# C-09_BOOT_CFG.net
KiCad netlist of a schematic drawn in Altium Designer
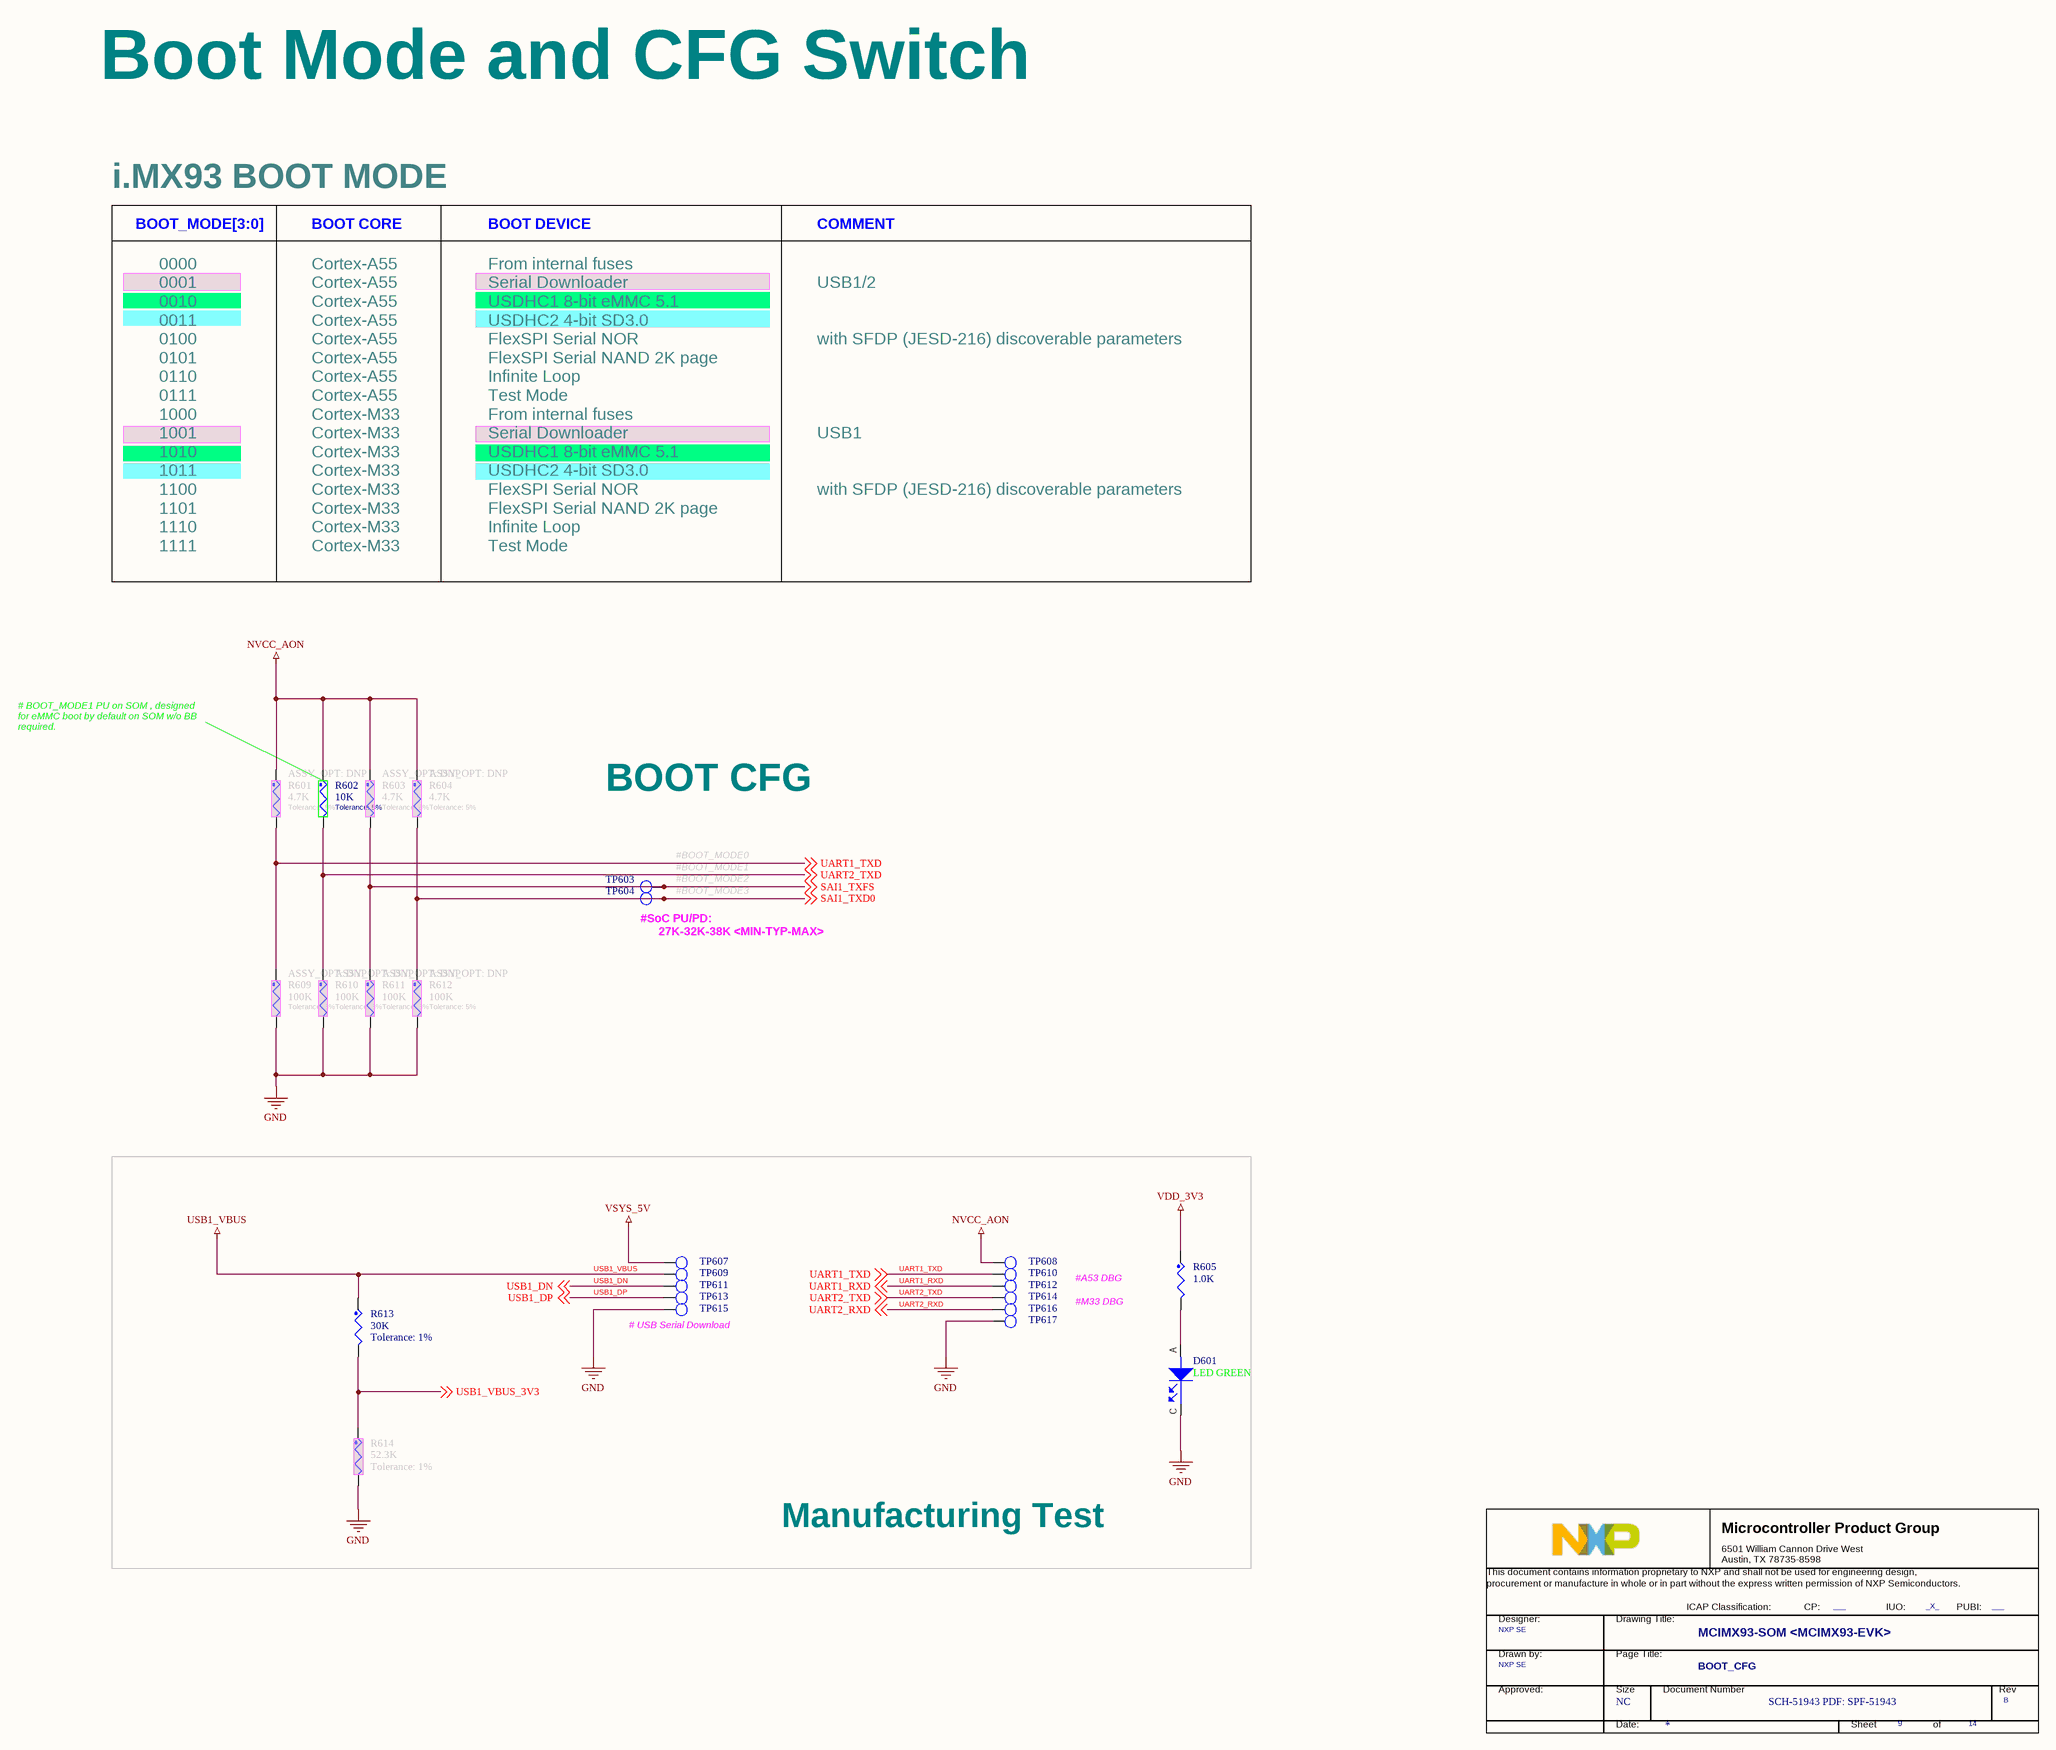
[diagram p0: C-09 BOOT_CFG.SchDoc]

(export (version "E")
  (design (tool "Eeschema 10.0.6"))
  (components
    (comp (ref "D601")
      (value "LED GREEN")
      (footprint "LED_0603")
      (description "LED GRN SGL 25MA SMT 0603")
      (fields (field (name "VOLTAGE") "2V"))
      (libsource (lib "*") (part "LED"))
    )
    (comp (ref "R601")
      (value "4.7K")
      (footprint "0402_CC")
      (description "RES MF 4.7K 1/10W 5% AEC-Q200 0402")
      (fields (field (name "ASSY_OPT") "DNP") (field (name "TOLERANCE") "5%") (field (name "VOLTAGE") "50V"))
      (libsource (lib "*") (part "RES"))
    )
    (comp (ref "R602")
      (value "10K")
      (footprint "0402_CC")
      (description "RES MF 10K 1/16W 5% 0402")
      (fields (field (name "TOLERANCE") "5%"))
      (libsource (lib "*") (part "RES"))
    )
    (comp (ref "R603")
      (value "4.7K")
      (footprint "0402_CC")
      (description "RES MF 4.7K 1/10W 5% AEC-Q200 0402")
      (fields (field (name "ASSY_OPT") "DNP") (field (name "VOLTAGE") "50V") (field (name "TOLERANCE") "5%"))
      (libsource (lib "*") (part "RES"))
    )
    (comp (ref "R604")
      (value "4.7K")
      (footprint "0402_CC")
      (description "RES MF 4.7K 1/10W 5% AEC-Q200 0402")
      (fields (field (name "ASSY_OPT") "DNP") (field (name "VOLTAGE") "50V") (field (name "TOLERANCE") "5%"))
      (libsource (lib "*") (part "RES"))
    )
    (comp (ref "R605")
      (value "1.0K")
      (footprint "0402_CC")
      (description "RES MF 1.0K 1/16W 1% 0402")
      (fields (field (name "VOLTAGE") "1/16W") (field (name "TOLERANCE") "1%"))
      (libsource (lib "*") (part "RES"))
    )
    (comp (ref "R609")
      (value "100K")
      (footprint "0402_CC")
      (description "RES MF 100K 1/16W 5% 0402")
      (fields (field (name "ASSY_OPT") "DNP") (field (name "TOLERANCE") "5%") (field (name "VOLTAGE") "50V"))
      (libsource (lib "*") (part "RES"))
    )
    (comp (ref "R610")
      (value "100K")
      (footprint "0402_CC")
      (description "RES MF 100K 1/16W 5% 0402")
      (fields (field (name "ASSY_OPT") "DNP") (field (name "TOLERANCE") "5%") (field (name "VOLTAGE") "50V"))
      (libsource (lib "*") (part "RES"))
    )
    (comp (ref "R611")
      (value "100K")
      (footprint "0402_CC")
      (description "RES MF 100K 1/16W 5% 0402")
      (fields (field (name "ASSY_OPT") "DNP") (field (name "TOLERANCE") "5%") (field (name "VOLTAGE") "50V"))
      (libsource (lib "*") (part "RES"))
    )
    (comp (ref "R612")
      (value "100K")
      (footprint "0402_CC")
      (description "RES MF 100K 1/16W 5% 0402")
      (fields (field (name "ASSY_OPT") "DNP") (field (name "TOLERANCE") "5%") (field (name "VOLTAGE") "50V"))
      (libsource (lib "*") (part "RES"))
    )
    (comp (ref "R613")
      (value "30K")
      (footprint "0402_CC")
      (description "RES MF 30K 1/10W 1% AEC-Q200 0402")
      (fields (field (name "VOLTAGE") "50V") (field (name "TOLERANCE") "1%"))
      (libsource (lib "*") (part "RES"))
    )
    (comp (ref "R614")
      (value "52.3K")
      (footprint "0201_CC")
      (description "RES MF 52.3K OHM 1% 1/20W 0201")
      (fields (field (name "TOLERANCE") "1%"))
      (libsource (lib "*") (part "RES"))
    )
    (comp (ref "TP603")
      (value "TP_35MIL")
      (footprint "testpoint_35mil")
      (description "TEST POINT PAD .035 SMT, no part to order")
      (libsource (lib "*") (part "T POINT R"))
    )
    (comp (ref "TP604")
      (value "TP_35MIL")
      (footprint "testpoint_35mil")
      (description "TEST POINT PAD .035 SMT, no part to order")
      (libsource (lib "*") (part "T POINT R"))
    )
    (comp (ref "TP607")
      (value "TP_35MIL")
      (footprint "testpoint_35mil")
      (description "TEST POINT PAD .035 SMT, no part to order")
      (libsource (lib "*") (part "T POINT R"))
    )
    (comp (ref "TP608")
      (value "TP_35MIL")
      (footprint "testpoint_35mil")
      (description "TEST POINT PAD .035 SMT, no part to order")
      (libsource (lib "*") (part "T POINT R"))
    )
    (comp (ref "TP609")
      (value "TP_35MIL")
      (footprint "testpoint_35mil")
      (description "TEST POINT PAD .035 SMT, no part to order")
      (libsource (lib "*") (part "T POINT R"))
    )
    (comp (ref "TP610")
      (value "TP_35MIL")
      (footprint "testpoint_35mil")
      (description "TEST POINT PAD .035 SMT, no part to order")
      (libsource (lib "*") (part "T POINT R"))
    )
    (comp (ref "TP611")
      (value "TP_35MIL")
      (footprint "testpoint_35mil")
      (description "TEST POINT PAD .035 SMT, no part to order")
      (libsource (lib "*") (part "T POINT R"))
    )
    (comp (ref "TP612")
      (value "TP_35MIL")
      (footprint "testpoint_35mil")
      (description "TEST POINT PAD .035 SMT, no part to order")
      (libsource (lib "*") (part "T POINT R"))
    )
    (comp (ref "TP613")
      (value "TP_35MIL")
      (footprint "testpoint_35mil")
      (description "TEST POINT PAD .035 SMT, no part to order")
      (libsource (lib "*") (part "T POINT R"))
    )
    (comp (ref "TP614")
      (value "TP_35MIL")
      (footprint "testpoint_35mil")
      (description "TEST POINT PAD .035 SMT, no part to order")
      (libsource (lib "*") (part "T POINT R"))
    )
    (comp (ref "TP615")
      (value "TP_35MIL")
      (footprint "testpoint_35mil")
      (description "TEST POINT PAD .035 SMT, no part to order")
      (libsource (lib "*") (part "T POINT R"))
    )
    (comp (ref "TP616")
      (value "TP_35MIL")
      (footprint "testpoint_35mil")
      (description "TEST POINT PAD .035 SMT, no part to order")
      (libsource (lib "*") (part "T POINT R"))
    )
    (comp (ref "TP617")
      (value "TP_35MIL")
      (footprint "testpoint_35mil")
      (description "TEST POINT PAD .035 SMT, no part to order")
      (libsource (lib "*") (part "T POINT R"))
    )
  )
  (nets
    (net (code "1") (name "GND") (class "Default")
      (node (ref "D601") (pin "C") (pinfunction "CATHODE_C") (pintype "passive"))
      (node (ref "R609") (pin "2") (pinfunction "2_2") (pintype "passive"))
      (node (ref "R610") (pin "2") (pinfunction "2_2") (pintype "passive"))
      (node (ref "R611") (pin "2") (pinfunction "2_2") (pintype "passive"))
      (node (ref "R612") (pin "2") (pinfunction "2_2") (pintype "passive"))
      (node (ref "R614") (pin "2") (pinfunction "2_2") (pintype "passive"))
      (node (ref "TP615") (pin "1") (pinfunction "TP_1") (pintype "passive"))
      (node (ref "TP617") (pin "1") (pinfunction "TP_1") (pintype "passive"))
    )
    (net (code "2") (name "NVCC_AON") (class "Default")
      (node (ref "R601") (pin "1") (pinfunction "1_1") (pintype "passive"))
      (node (ref "R602") (pin "1") (pinfunction "1_1") (pintype "passive"))
      (node (ref "R603") (pin "1") (pinfunction "1_1") (pintype "passive"))
      (node (ref "R604") (pin "1") (pinfunction "1_1") (pintype "passive"))
      (node (ref "TP608") (pin "1") (pinfunction "TP_1") (pintype "passive"))
    )
    (net (code "3") (name "Net-(D601-ANODE)") (class "Default")
      (node (ref "D601") (pin "A") (pinfunction "ANODE_A") (pintype "passive"))
      (node (ref "R605") (pin "2") (pinfunction "2_2") (pintype "passive"))
    )
    (net (code "4") (name "SAI1_TXD0") (class "Default")
      (node (ref "R604") (pin "2") (pinfunction "2_2") (pintype "passive"))
      (node (ref "R612") (pin "1") (pinfunction "1_1") (pintype "passive"))
      (node (ref "TP604") (pin "1") (pinfunction "TP_1") (pintype "passive"))
    )
    (net (code "5") (name "SAI1_TXFS") (class "Default")
      (node (ref "R603") (pin "2") (pinfunction "2_2") (pintype "passive"))
      (node (ref "R611") (pin "1") (pinfunction "1_1") (pintype "passive"))
      (node (ref "TP603") (pin "1") (pinfunction "TP_1") (pintype "passive"))
    )
    (net (code "6") (name "UART1_RXD") (class "Default")
      (node (ref "TP612") (pin "1") (pinfunction "TP_1") (pintype "passive"))
    )
    (net (code "7") (name "UART1_TXD") (class "Default")
      (node (ref "R601") (pin "2") (pinfunction "2_2") (pintype "passive"))
      (node (ref "R609") (pin "1") (pinfunction "1_1") (pintype "passive"))
      (node (ref "TP610") (pin "1") (pinfunction "TP_1") (pintype "passive"))
    )
    (net (code "8") (name "UART2_RXD") (class "Default")
      (node (ref "TP616") (pin "1") (pinfunction "TP_1") (pintype "passive"))
    )
    (net (code "9") (name "UART2_TXD") (class "Default")
      (node (ref "R602") (pin "2") (pinfunction "2_2") (pintype "passive"))
      (node (ref "R610") (pin "1") (pinfunction "1_1") (pintype "passive"))
      (node (ref "TP614") (pin "1") (pinfunction "TP_1") (pintype "passive"))
    )
    (net (code "10") (name "USB1_DN") (class "Default")
      (node (ref "TP611") (pin "1") (pinfunction "TP_1") (pintype "passive"))
    )
    (net (code "11") (name "USB1_DP") (class "Default")
      (node (ref "TP613") (pin "1") (pinfunction "TP_1") (pintype "passive"))
    )
    (net (code "12") (name "USB1_VBUS") (class "Default")
      (node (ref "R613") (pin "1") (pinfunction "1_1") (pintype "passive"))
      (node (ref "TP609") (pin "1") (pinfunction "TP_1") (pintype "passive"))
    )
    (net (code "13") (name "USB1_VBUS_3V3") (class "Default")
      (node (ref "R613") (pin "2") (pinfunction "2_2") (pintype "passive"))
      (node (ref "R614") (pin "1") (pinfunction "1_1") (pintype "passive"))
    )
    (net (code "14") (name "VDD_3V3") (class "Default")
      (node (ref "R605") (pin "1") (pinfunction "1_1") (pintype "passive"))
    )
    (net (code "15") (name "VSYS_5V") (class "Default")
      (node (ref "TP607") (pin "1") (pinfunction "TP_1") (pintype "passive"))
    )
  )
)
